# nau7802.net
KiCad netlist of a schematic drawn in EAGLE
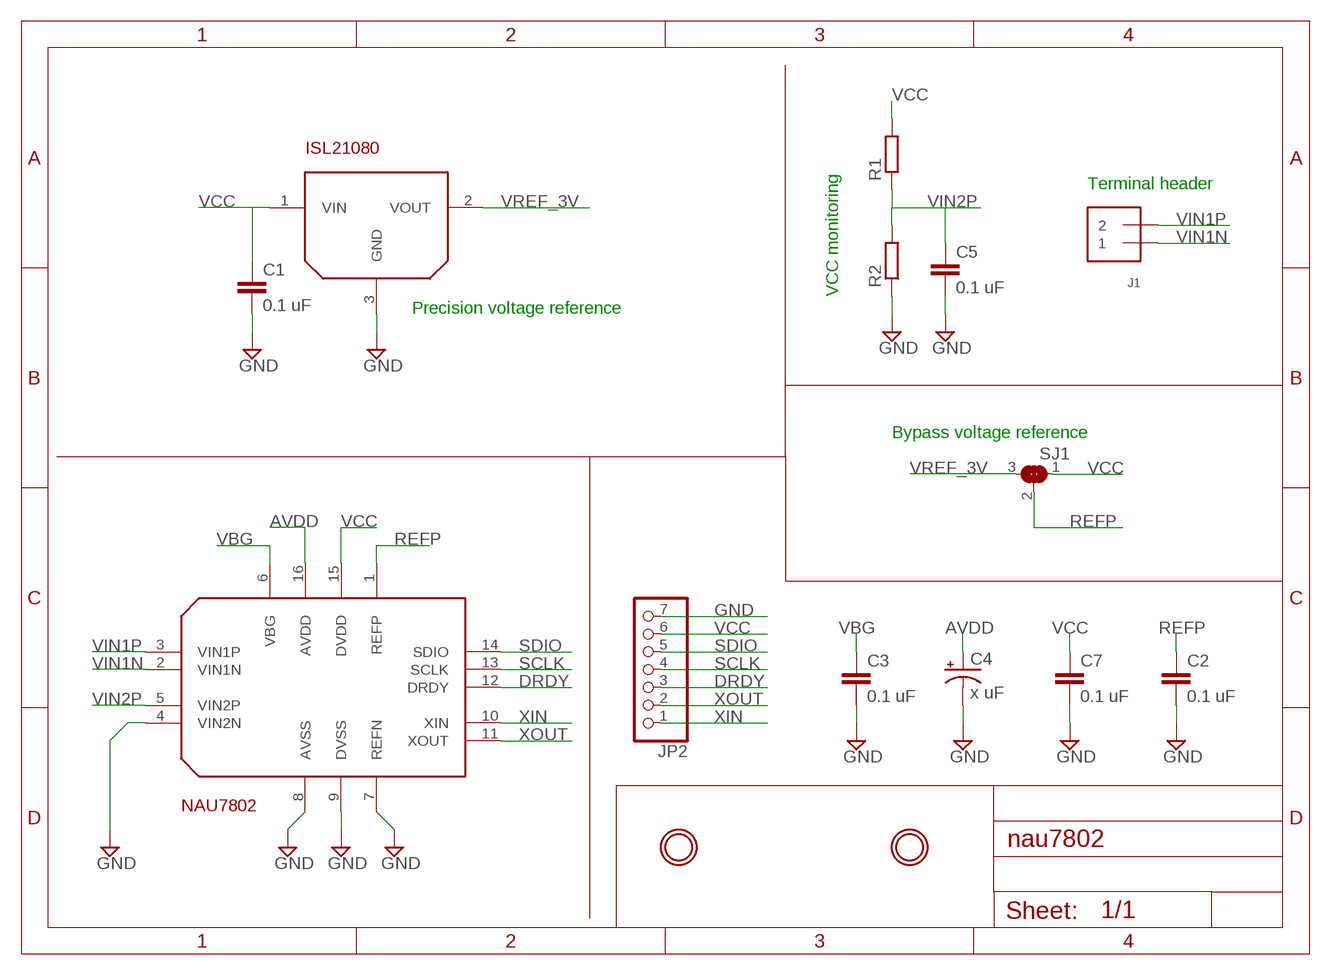
[diagram p0: schematic, sheet 1]

(export (version "E")
  (design (tool "Eeschema 10.0.6"))
  (components
    (comp (ref "C1")
      (value "0.1 uF")
      (footprint "eagle-import:C0805")
      (libsource (lib "eagle-import") (part "C-EUC0805"))
    )
    (comp (ref "C2")
      (value "0.1 uF")
      (footprint "eagle-import:C0805")
      (libsource (lib "eagle-import") (part "C-EUC0805"))
    )
    (comp (ref "C3")
      (value "0.1 uF")
      (footprint "eagle-import:C0805")
      (libsource (lib "eagle-import") (part "C-EUC0805"))
    )
    (comp (ref "C4")
      (value "x uF")
      (footprint "eagle-import:D_7343-31W")
      (libsource (lib "eagle-import") (part "CPOL-USD/7343-31W"))
    )
    (comp (ref "C5")
      (value "0.1 uF")
      (footprint "eagle-import:C0805")
      (libsource (lib "eagle-import") (part "C-EUC0805"))
    )
    (comp (ref "C7")
      (value "0.1 uF")
      (footprint "eagle-import:C0805")
      (libsource (lib "eagle-import") (part "C-EUC0805"))
    )
    (comp (ref "J1")
      (value "TERMBLOCK_1X2")
      (footprint "eagle-import:TERMBLOCK_1X2-3.5MM")
      (libsource (lib "eagle-import") (part "TERMBLOCK_1X2"))
    )
    (comp (ref "JP2")
      (value "PINHD-1X7")
      (footprint "eagle-import:1X07")
      (libsource (lib "eagle-import") (part "PINHD-1X7"))
    )
    (comp (ref "R1")
      (value "R-EU_R0805")
      (footprint "eagle-import:R0805")
      (libsource (lib "eagle-import") (part "R-EU_R0805"))
    )
    (comp (ref "R2")
      (value "R-EU_R0805")
      (footprint "eagle-import:R0805")
      (libsource (lib "eagle-import") (part "R-EU_R0805"))
    )
    (comp (ref "SJ1")
      (value "SOLDERJUMPER_2WAY0805")
      (footprint "eagle-import:SOLDERJUMPER_2WAY_OPEN_0805")
      (libsource (lib "eagle-import") (part "SOLDERJUMPER_2WAY0805"))
    )
    (comp (ref "U$1")
      (value "IHSAN_NAU7802")
      (footprint "eagle-import:SO16")
      (libsource (lib "eagle-import") (part "IHSAN_NAU7802"))
    )
    (comp (ref "U$3")
      (value "IHSAN_ISL21080")
      (footprint "eagle-import:SOT23-3")
      (libsource (lib "eagle-import") (part "IHSAN_ISL21080"))
    )
    (comp (ref "U$4")
      (value "MOUNTINGHOLE3.0THIN")
      (footprint "eagle-import:MOUNTINGHOLE_3.0_PLATEDTHIN")
      (libsource (lib "eagle-import") (part "MOUNTINGHOLE3.0THIN"))
    )
    (comp (ref "U$5")
      (value "MOUNTINGHOLE3.0THIN")
      (footprint "eagle-import:MOUNTINGHOLE_3.0_PLATEDTHIN")
      (libsource (lib "eagle-import") (part "MOUNTINGHOLE3.0THIN"))
    )
  )
  (nets
    (net (code "1") (name "/AVDD") (class "Default")
      (node (ref "C4") (pin "+") (pinfunction "+_+") (pintype "passive"))
      (node (ref "U$1") (pin "16") (pinfunction "AVDD_16") (pintype "bidirectional"))
    )
    (net (code "2") (name "/DRDY") (class "Default")
      (node (ref "JP2") (pin "3") (pinfunction "3_3") (pintype "passive"))
      (node (ref "U$1") (pin "12") (pinfunction "DRDY_12") (pintype "bidirectional"))
    )
    (net (code "3") (name "/REFP") (class "Default")
      (node (ref "C2") (pin "1") (pinfunction "1_1") (pintype "passive"))
      (node (ref "SJ1") (pin "2") (pinfunction "2_2") (pintype "passive"))
      (node (ref "U$1") (pin "1") (pinfunction "REFP_1") (pintype "bidirectional"))
    )
    (net (code "4") (name "/SCLK") (class "Default")
      (node (ref "JP2") (pin "4") (pinfunction "4_4") (pintype "passive"))
      (node (ref "U$1") (pin "13") (pinfunction "SCLK_13") (pintype "bidirectional"))
    )
    (net (code "5") (name "/SDIO") (class "Default")
      (node (ref "JP2") (pin "5") (pinfunction "5_5") (pintype "passive"))
      (node (ref "U$1") (pin "14") (pinfunction "SDIO_14") (pintype "bidirectional"))
    )
    (net (code "6") (name "/VBG") (class "Default")
      (node (ref "C3") (pin "1") (pinfunction "1_1") (pintype "passive"))
      (node (ref "U$1") (pin "6") (pinfunction "VBG_6") (pintype "bidirectional"))
    )
    (net (code "7") (name "/VCC") (class "Default")
      (node (ref "C1") (pin "1") (pinfunction "1_1") (pintype "passive"))
      (node (ref "C7") (pin "1") (pinfunction "1_1") (pintype "passive"))
      (node (ref "JP2") (pin "6") (pinfunction "6_6") (pintype "passive"))
      (node (ref "R1") (pin "2") (pinfunction "2_2") (pintype "passive"))
      (node (ref "SJ1") (pin "1") (pinfunction "1_1") (pintype "passive"))
      (node (ref "U$1") (pin "15") (pinfunction "DVDD_15") (pintype "bidirectional"))
      (node (ref "U$3") (pin "1") (pinfunction "VIN_1") (pintype "bidirectional"))
    )
    (net (code "8") (name "/VIN1N") (class "Default")
      (node (ref "J1") (pin "1") (pinfunction "1_1") (pintype "passive"))
      (node (ref "U$1") (pin "2") (pinfunction "VIN1N_2") (pintype "bidirectional"))
    )
    (net (code "9") (name "/VIN1P") (class "Default")
      (node (ref "J1") (pin "2") (pinfunction "2_2") (pintype "passive"))
      (node (ref "U$1") (pin "3") (pinfunction "VIN1P_3") (pintype "bidirectional"))
    )
    (net (code "10") (name "/VIN2P") (class "Default")
      (node (ref "C5") (pin "1") (pinfunction "1_1") (pintype "passive"))
      (node (ref "R1") (pin "1") (pinfunction "1_1") (pintype "passive"))
      (node (ref "R2") (pin "2") (pinfunction "2_2") (pintype "passive"))
      (node (ref "U$1") (pin "5") (pinfunction "VIN2P_5") (pintype "bidirectional"))
    )
    (net (code "11") (name "/VREF_3V") (class "Default")
      (node (ref "SJ1") (pin "3") (pinfunction "3_3") (pintype "passive"))
      (node (ref "U$3") (pin "2") (pinfunction "VOUT_2") (pintype "bidirectional"))
    )
    (net (code "12") (name "/XIN") (class "Default")
      (node (ref "JP2") (pin "1") (pinfunction "1_1") (pintype "passive"))
      (node (ref "U$1") (pin "10") (pinfunction "XIN_10") (pintype "bidirectional"))
    )
    (net (code "13") (name "/XOUT") (class "Default")
      (node (ref "JP2") (pin "2") (pinfunction "2_2") (pintype "passive"))
      (node (ref "U$1") (pin "11") (pinfunction "XOUT_11") (pintype "bidirectional"))
    )
    (net (code "14") (name "GND") (class "Default")
      (node (ref "C1") (pin "2") (pinfunction "2_2") (pintype "passive"))
      (node (ref "C2") (pin "2") (pinfunction "2_2") (pintype "passive"))
      (node (ref "C3") (pin "2") (pinfunction "2_2") (pintype "passive"))
      (node (ref "C4") (pin "-") (pinfunction "-_-") (pintype "passive"))
      (node (ref "C5") (pin "2") (pinfunction "2_2") (pintype "passive"))
      (node (ref "C7") (pin "2") (pinfunction "2_2") (pintype "passive"))
      (node (ref "JP2") (pin "7") (pinfunction "7_7") (pintype "passive"))
      (node (ref "R2") (pin "1") (pinfunction "1_1") (pintype "passive"))
      (node (ref "U$1") (pin "4") (pinfunction "VIN2N_4") (pintype "bidirectional"))
      (node (ref "U$1") (pin "7") (pinfunction "REFN_7") (pintype "bidirectional"))
      (node (ref "U$1") (pin "8") (pinfunction "AVSS_8") (pintype "bidirectional"))
      (node (ref "U$1") (pin "9") (pinfunction "DVSS_9") (pintype "bidirectional"))
      (node (ref "U$3") (pin "3") (pinfunction "GND_3") (pintype "bidirectional"))
    )
  )
)
